# Nixie_Driver.net
KiCad netlist of a schematic drawn in Altium Designer
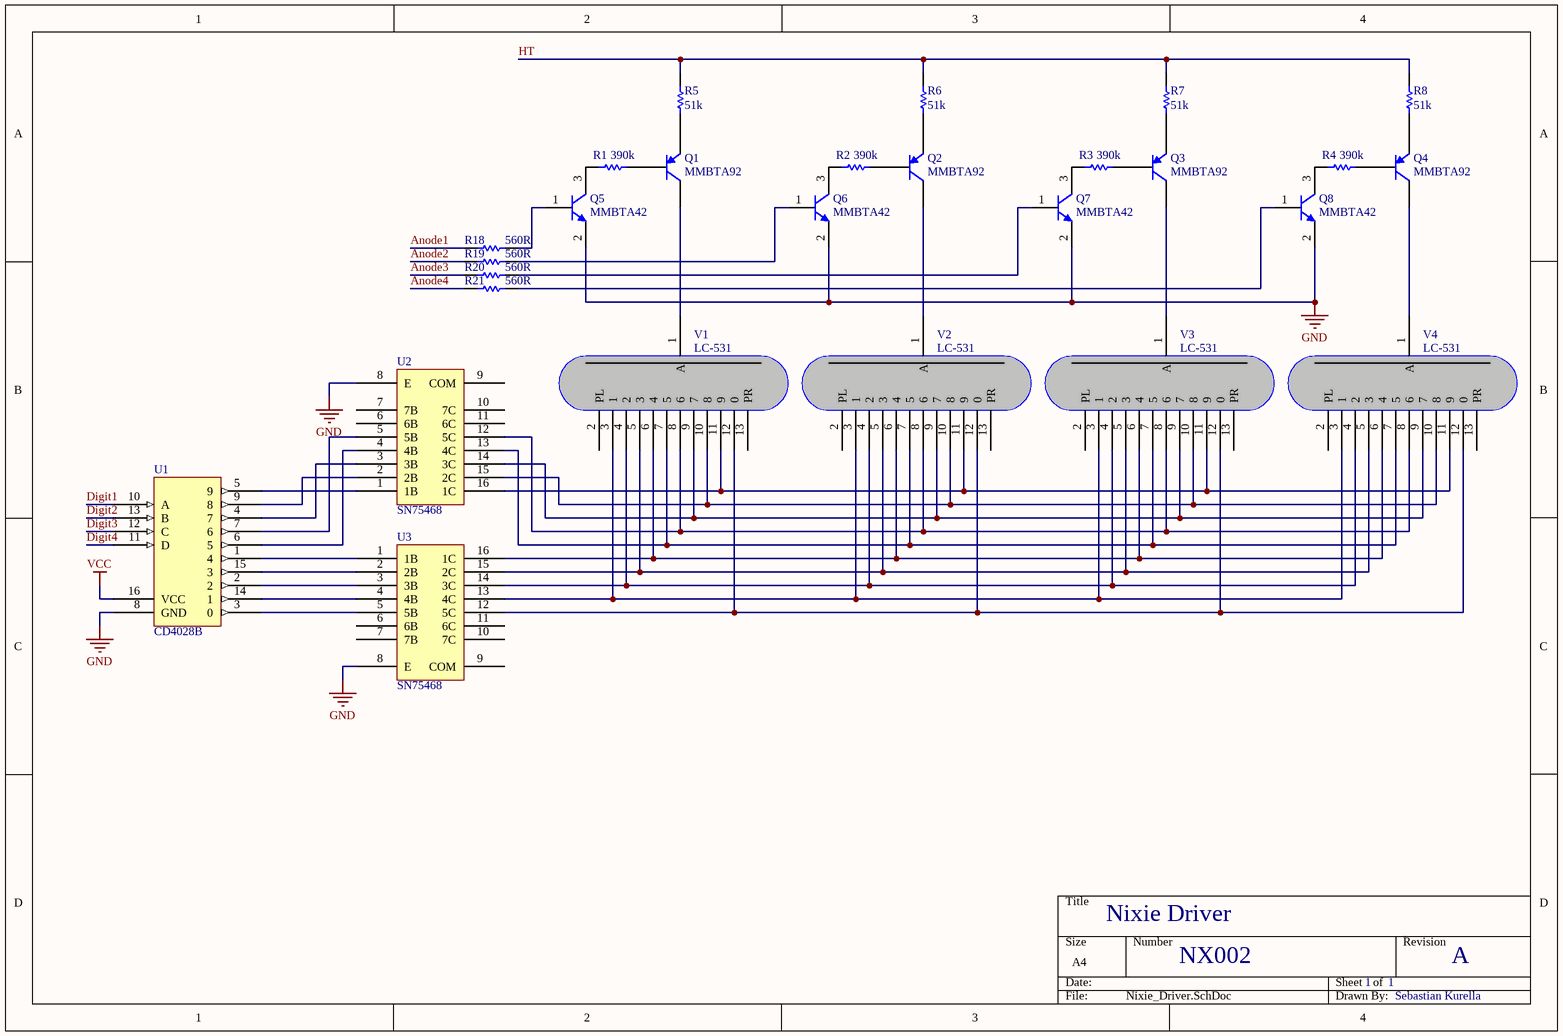
[diagram p0: Nixie_Driver.SchDoc]

(export (version "E")
  (design (tool "Eeschema 10.0.6"))
  (components
    (comp (ref "Q1")
      (value "MMBTA92")
      (footprint "INF-SOT23_M")
      (description "PNP Silicon High-Voltage Transistor, 300 V VCEO, 500 mA IC, SOT23, Reel, Green")
      (fields (field (name "MANUFACTURER") "Infineon"))
      (libsource (lib "Altium Content Vault") (part "CMP-1197-00010-1"))
    )
    (comp (ref "Q2")
      (value "MMBTA92")
      (footprint "INF-SOT23_M")
      (description "PNP Silicon High-Voltage Transistor, 300 V VCEO, 500 mA IC, SOT23, Reel, Green")
      (fields (field (name "MANUFACTURER") "Infineon"))
      (libsource (lib "Altium Content Vault") (part "CMP-1197-00010-1"))
    )
    (comp (ref "Q3")
      (value "MMBTA92")
      (footprint "INF-SOT23_M")
      (description "PNP Silicon High-Voltage Transistor, 300 V VCEO, 500 mA IC, SOT23, Reel, Green")
      (fields (field (name "MANUFACTURER") "Infineon"))
      (libsource (lib "Altium Content Vault") (part "CMP-1197-00010-1"))
    )
    (comp (ref "Q4")
      (value "MMBTA92")
      (footprint "INF-SOT23_M")
      (description "PNP Silicon High-Voltage Transistor, 300 V VCEO, 500 mA IC, SOT23, Reel, Green")
      (fields (field (name "MANUFACTURER") "Infineon"))
      (libsource (lib "Altium Content Vault") (part "CMP-1197-00010-1"))
    )
    (comp (ref "Q5")
      (value "MMBTA42")
      (footprint "ONSC-SOT-23-3-318-08_V")
      (description "High Voltage Transistor, NPN Silicon, 3-Pin SOT-23, Pb-Free, Tape and Reel")
      (fields (field (name "MANUFACTURER") "On Semiconductor"))
      (libsource (lib "Altium Content Vault") (part "CMP-1048-00662-1"))
    )
    (comp (ref "Q6")
      (value "MMBTA42")
      (footprint "ONSC-SOT-23-3-318-08_V")
      (description "High Voltage Transistor, NPN Silicon, 3-Pin SOT-23, Pb-Free, Tape and Reel")
      (fields (field (name "MANUFACTURER") "On Semiconductor"))
      (libsource (lib "Altium Content Vault") (part "CMP-1048-00662-1"))
    )
    (comp (ref "Q7")
      (value "MMBTA42")
      (footprint "ONSC-SOT-23-3-318-08_V")
      (description "High Voltage Transistor, NPN Silicon, 3-Pin SOT-23, Pb-Free, Tape and Reel")
      (fields (field (name "MANUFACTURER") "On Semiconductor"))
      (libsource (lib "Altium Content Vault") (part "CMP-1048-00662-1"))
    )
    (comp (ref "Q8")
      (value "MMBTA42")
      (footprint "ONSC-SOT-23-3-318-08_V")
      (description "High Voltage Transistor, NPN Silicon, 3-Pin SOT-23, Pb-Free, Tape and Reel")
      (fields (field (name "MANUFACTURER") "On Semiconductor"))
      (libsource (lib "Altium Content Vault") (part "CMP-1048-00662-1"))
    )
    (comp (ref "R1")
      (value "390k")
      (footprint "RESC0805(2012)_M")
      (description "390K 0.125W 5% 0805 (2012 Metric)  SMD")
      (fields (field (name "TOLERANCE") "5 %") (field (name "POWER") "0.125 W"))
      (libsource (lib "Altium Content Vault") (part "CMP-1013-00136-1"))
    )
    (comp (ref "R2")
      (value "390k")
      (footprint "RESC0805(2012)_M")
      (description "390K 0.125W 5% 0805 (2012 Metric)  SMD")
      (fields (field (name "TOLERANCE") "5 %") (field (name "POWER") "0.125 W"))
      (libsource (lib "Altium Content Vault") (part "CMP-1013-00136-1"))
    )
    (comp (ref "R3")
      (value "390k")
      (footprint "RESC0805(2012)_M")
      (description "390K 0.125W 5% 0805 (2012 Metric)  SMD")
      (fields (field (name "TOLERANCE") "5 %") (field (name "POWER") "0.125 W"))
      (libsource (lib "Altium Content Vault") (part "CMP-1013-00136-1"))
    )
    (comp (ref "R4")
      (value "390k")
      (footprint "RESC0805(2012)_M")
      (description "390K 0.125W 5% 0805 (2012 Metric)  SMD")
      (fields (field (name "TOLERANCE") "5 %") (field (name "POWER") "0.125 W"))
      (libsource (lib "Altium Content Vault") (part "CMP-1013-00136-1"))
    )
    (comp (ref "R5")
      (value "51k")
      (footprint "RESC0805(2012)_M")
      (description "51K 0.125W 5% 0805 (2012 Metric)  SMD")
      (fields (field (name "POWER") "0.125 W") (field (name "TOLERANCE") "5 %"))
      (libsource (lib "Altium Content Vault") (part "CMP-1013-00115-1"))
    )
    (comp (ref "R6")
      (value "51k")
      (footprint "RESC0805(2012)_M")
      (description "51K 0.125W 5% 0805 (2012 Metric)  SMD")
      (fields (field (name "POWER") "0.125 W") (field (name "TOLERANCE") "5 %"))
      (libsource (lib "Altium Content Vault") (part "CMP-1013-00115-1"))
    )
    (comp (ref "R7")
      (value "51k")
      (footprint "RESC0805(2012)_M")
      (description "51K 0.125W 5% 0805 (2012 Metric)  SMD")
      (fields (field (name "POWER") "0.125 W") (field (name "TOLERANCE") "5 %"))
      (libsource (lib "Altium Content Vault") (part "CMP-1013-00115-1"))
    )
    (comp (ref "R8")
      (value "51k")
      (footprint "RESC0805(2012)_M")
      (description "51K 0.125W 5% 0805 (2012 Metric)  SMD")
      (fields (field (name "POWER") "0.125 W") (field (name "TOLERANCE") "5 %"))
      (libsource (lib "Altium Content Vault") (part "CMP-1013-00115-1"))
    )
    (comp (ref "R18")
      (value "560R")
      (footprint "RESC0805(2012)_M")
      (description "560R 0.125W 5% 0805 (2012 Metric)  SMD")
      (fields (field (name "POWER") "0.125 W") (field (name "TOLERANCE") "5 %"))
      (libsource (lib "Altium Content Vault") (part "CMP-1013-00068-1"))
    )
    (comp (ref "R19")
      (value "560R")
      (footprint "RESC0805(2012)_M")
      (description "560R 0.125W 5% 0805 (2012 Metric)  SMD")
      (fields (field (name "POWER") "0.125 W") (field (name "TOLERANCE") "5 %"))
      (libsource (lib "Altium Content Vault") (part "CMP-1013-00068-1"))
    )
    (comp (ref "R20")
      (value "560R")
      (footprint "RESC0805(2012)_M")
      (description "560R 0.125W 5% 0805 (2012 Metric)  SMD")
      (fields (field (name "POWER") "0.125 W") (field (name "TOLERANCE") "5 %"))
      (libsource (lib "Altium Content Vault") (part "CMP-1013-00068-1"))
    )
    (comp (ref "R21")
      (value "560R")
      (footprint "RESC0805(2012)_M")
      (description "560R 0.125W 5% 0805 (2012 Metric)  SMD")
      (fields (field (name "POWER") "0.125 W") (field (name "TOLERANCE") "5 %"))
      (libsource (lib "Altium Content Vault") (part "CMP-1013-00068-1"))
    )
    (comp (ref "U1")
      (value "CD4028B")
      (footprint "CD4028B")
      (description "BCD-to-decimal driver")
      (libsource (lib "Nixie_Driver") (part "CD4028B"))
    )
    (comp (ref "U2")
      (value "SN75468")
      (footprint "SN7546x")
      (description "Darlington Transistor Array")
      (libsource (lib "") (part "SN7546x_1"))
    )
    (comp (ref "U3")
      (value "SN75468")
      (footprint "SN7546x")
      (description "Darlington Transistor Array")
      (libsource (lib "Nixie_Driver") (part "SN7546x"))
    )
    (comp (ref "V1")
      (value "LC-531")
      (footprint "LC-531")
      (description "Nixie tube")
      (libsource (lib "Nixie_Driver") (part "LC531"))
    )
    (comp (ref "V2")
      (value "LC-531")
      (footprint "LC-531")
      (description "Nixie tube")
      (libsource (lib "Nixie_Driver") (part "LC531"))
    )
    (comp (ref "V3")
      (value "LC-531")
      (footprint "LC-531")
      (description "Nixie tube")
      (libsource (lib "Nixie_Driver") (part "LC531"))
    )
    (comp (ref "V4")
      (value "LC-531")
      (footprint "LC-531")
      (description "Nixie tube")
      (libsource (lib "Nixie_Driver") (part "LC531"))
    )
  )
  (nets
    (net (code "1") (name "/Anode1") (class "Default")
      (node (ref "R18") (pin "1") (pinfunction "1_1") (pintype "passive"))
    )
    (net (code "2") (name "/Anode2") (class "Default")
      (node (ref "R19") (pin "1") (pinfunction "1_1") (pintype "passive"))
    )
    (net (code "3") (name "/Anode3") (class "Default")
      (node (ref "R20") (pin "1") (pinfunction "1_1") (pintype "passive"))
    )
    (net (code "4") (name "/Anode4") (class "Default")
      (node (ref "R21") (pin "1") (pinfunction "1_1") (pintype "passive"))
    )
    (net (code "5") (name "/Digit1") (class "Default")
      (node (ref "U1") (pin "10") (pinfunction "A_10") (pintype "input"))
    )
    (net (code "6") (name "/Digit2") (class "Default")
      (node (ref "U1") (pin "13") (pinfunction "B_13") (pintype "input"))
    )
    (net (code "7") (name "/Digit3") (class "Default")
      (node (ref "U1") (pin "12") (pinfunction "C_12") (pintype "input"))
    )
    (net (code "8") (name "/Digit4") (class "Default")
      (node (ref "U1") (pin "11") (pinfunction "D_11") (pintype "input"))
    )
    (net (code "9") (name "/HT") (class "Default")
      (node (ref "R5") (pin "2") (pinfunction "2_2") (pintype "passive"))
      (node (ref "R6") (pin "2") (pinfunction "2_2") (pintype "passive"))
      (node (ref "R7") (pin "2") (pinfunction "2_2") (pintype "passive"))
      (node (ref "R8") (pin "2") (pinfunction "2_2") (pintype "passive"))
    )
    (net (code "10") (name "GND") (class "Default")
      (node (ref "Q5") (pin "2") (pinfunction "E_2") (pintype "passive"))
      (node (ref "Q6") (pin "2") (pinfunction "E_2") (pintype "passive"))
      (node (ref "Q7") (pin "2") (pinfunction "E_2") (pintype "passive"))
      (node (ref "Q8") (pin "2") (pinfunction "E_2") (pintype "passive"))
      (node (ref "U1") (pin "8") (pinfunction "GND_8") (pintype "power_in"))
      (node (ref "U2") (pin "8") (pinfunction "E_8") (pintype "passive"))
      (node (ref "U3") (pin "8") (pinfunction "E_8") (pintype "passive"))
    )
    (net (code "11") (name "Net-(Q1-B)") (class "Default")
      (node (ref "Q1") (pin "1") (pinfunction "B_1") (pintype "passive"))
      (node (ref "R1") (pin "2") (pinfunction "2_2") (pintype "passive"))
    )
    (net (code "12") (name "Net-(Q1-C)") (class "Default")
      (node (ref "Q1") (pin "3") (pinfunction "C_3") (pintype "passive"))
      (node (ref "V1") (pin "1") (pinfunction "A_1") (pintype "passive"))
    )
    (net (code "13") (name "Net-(Q1-E)") (class "Default")
      (node (ref "Q1") (pin "2") (pinfunction "E_2") (pintype "passive"))
      (node (ref "R5") (pin "1") (pinfunction "1_1") (pintype "passive"))
    )
    (net (code "14") (name "Net-(Q2-B)") (class "Default")
      (node (ref "Q2") (pin "1") (pinfunction "B_1") (pintype "passive"))
      (node (ref "R2") (pin "2") (pinfunction "2_2") (pintype "passive"))
    )
    (net (code "15") (name "Net-(Q2-C)") (class "Default")
      (node (ref "Q2") (pin "3") (pinfunction "C_3") (pintype "passive"))
      (node (ref "V2") (pin "1") (pinfunction "A_1") (pintype "passive"))
    )
    (net (code "16") (name "Net-(Q2-E)") (class "Default")
      (node (ref "Q2") (pin "2") (pinfunction "E_2") (pintype "passive"))
      (node (ref "R6") (pin "1") (pinfunction "1_1") (pintype "passive"))
    )
    (net (code "17") (name "Net-(Q3-B)") (class "Default")
      (node (ref "Q3") (pin "1") (pinfunction "B_1") (pintype "passive"))
      (node (ref "R3") (pin "2") (pinfunction "2_2") (pintype "passive"))
    )
    (net (code "18") (name "Net-(Q3-C)") (class "Default")
      (node (ref "Q3") (pin "3") (pinfunction "C_3") (pintype "passive"))
      (node (ref "V3") (pin "1") (pinfunction "A_1") (pintype "passive"))
    )
    (net (code "19") (name "Net-(Q3-E)") (class "Default")
      (node (ref "Q3") (pin "2") (pinfunction "E_2") (pintype "passive"))
      (node (ref "R7") (pin "1") (pinfunction "1_1") (pintype "passive"))
    )
    (net (code "20") (name "Net-(Q4-B)") (class "Default")
      (node (ref "Q4") (pin "1") (pinfunction "B_1") (pintype "passive"))
      (node (ref "R4") (pin "2") (pinfunction "2_2") (pintype "passive"))
    )
    (net (code "21") (name "Net-(Q4-C)") (class "Default")
      (node (ref "Q4") (pin "3") (pinfunction "C_3") (pintype "passive"))
      (node (ref "V4") (pin "1") (pinfunction "A_1") (pintype "passive"))
    )
    (net (code "22") (name "Net-(Q4-E)") (class "Default")
      (node (ref "Q4") (pin "2") (pinfunction "E_2") (pintype "passive"))
      (node (ref "R8") (pin "1") (pinfunction "1_1") (pintype "passive"))
    )
    (net (code "23") (name "Net-(Q5-B)") (class "Default")
      (node (ref "Q5") (pin "1") (pinfunction "B_1") (pintype "passive"))
      (node (ref "R18") (pin "2") (pinfunction "2_2") (pintype "passive"))
    )
    (net (code "24") (name "Net-(Q5-C)") (class "Default")
      (node (ref "Q5") (pin "3") (pinfunction "C_3") (pintype "passive"))
      (node (ref "R1") (pin "1") (pinfunction "1_1") (pintype "passive"))
    )
    (net (code "25") (name "Net-(Q6-B)") (class "Default")
      (node (ref "Q6") (pin "1") (pinfunction "B_1") (pintype "passive"))
      (node (ref "R19") (pin "2") (pinfunction "2_2") (pintype "passive"))
    )
    (net (code "26") (name "Net-(Q6-C)") (class "Default")
      (node (ref "Q6") (pin "3") (pinfunction "C_3") (pintype "passive"))
      (node (ref "R2") (pin "1") (pinfunction "1_1") (pintype "passive"))
    )
    (net (code "27") (name "Net-(Q7-B)") (class "Default")
      (node (ref "Q7") (pin "1") (pinfunction "B_1") (pintype "passive"))
      (node (ref "R20") (pin "2") (pinfunction "2_2") (pintype "passive"))
    )
    (net (code "28") (name "Net-(Q7-C)") (class "Default")
      (node (ref "Q7") (pin "3") (pinfunction "C_3") (pintype "passive"))
      (node (ref "R3") (pin "1") (pinfunction "1_1") (pintype "passive"))
    )
    (net (code "29") (name "Net-(Q8-B)") (class "Default")
      (node (ref "Q8") (pin "1") (pinfunction "B_1") (pintype "passive"))
      (node (ref "R21") (pin "2") (pinfunction "2_2") (pintype "passive"))
    )
    (net (code "30") (name "Net-(Q8-C)") (class "Default")
      (node (ref "Q8") (pin "3") (pinfunction "C_3") (pintype "passive"))
      (node (ref "R4") (pin "1") (pinfunction "1_1") (pintype "passive"))
    )
    (net (code "31") (name "Net-(U1-0)") (class "Default")
      (node (ref "U1") (pin "3") (pinfunction "0_3") (pintype "output"))
      (node (ref "U3") (pin "5") (pinfunction "5B_5") (pintype "passive"))
    )
    (net (code "32") (name "Net-(U1-1)") (class "Default")
      (node (ref "U1") (pin "14") (pinfunction "1_14") (pintype "output"))
      (node (ref "U3") (pin "4") (pinfunction "4B_4") (pintype "passive"))
    )
    (net (code "33") (name "Net-(U1-3)") (class "Default")
      (node (ref "U1") (pin "15") (pinfunction "3_15") (pintype "output"))
      (node (ref "U3") (pin "2") (pinfunction "2B_2") (pintype "passive"))
    )
    (net (code "34") (name "Net-(U1-4)") (class "Default")
      (node (ref "U1") (pin "1") (pinfunction "4_1") (pintype "output"))
      (node (ref "U3") (pin "1") (pinfunction "1B_1") (pintype "passive"))
    )
    (net (code "35") (name "Net-(U1-5)") (class "Default")
      (node (ref "U1") (pin "6") (pinfunction "5_6") (pintype "output"))
      (node (ref "U2") (pin "4") (pinfunction "4B_4") (pintype "passive"))
    )
    (net (code "36") (name "Net-(U1-6)") (class "Default")
      (node (ref "U1") (pin "7") (pinfunction "6_7") (pintype "output"))
      (node (ref "U2") (pin "5") (pinfunction "5B_5") (pintype "passive"))
    )
    (net (code "37") (name "Net-(U1-7)") (class "Default")
      (node (ref "U1") (pin "4") (pinfunction "7_4") (pintype "output"))
      (node (ref "U2") (pin "3") (pinfunction "3B_3") (pintype "passive"))
    )
    (net (code "38") (name "Net-(U1-8)") (class "Default")
      (node (ref "U1") (pin "9") (pinfunction "8_9") (pintype "output"))
      (node (ref "U2") (pin "2") (pinfunction "2B_2") (pintype "passive"))
    )
    (net (code "39") (name "Net-(U1-9)") (class "Default")
      (node (ref "U1") (pin "5") (pinfunction "9_5") (pintype "output"))
      (node (ref "U2") (pin "1") (pinfunction "1B_1") (pintype "passive"))
    )
    (net (code "40") (name "Net-(U2-1C)") (class "Default")
      (node (ref "U2") (pin "16") (pinfunction "1C_16") (pintype "passive"))
      (node (ref "V1") (pin "11") (pinfunction "9_11") (pintype "passive"))
      (node (ref "V2") (pin "11") (pinfunction "9_11") (pintype "passive"))
      (node (ref "V3") (pin "11") (pinfunction "9_11") (pintype "passive"))
      (node (ref "V4") (pin "11") (pinfunction "9_11") (pintype "passive"))
    )
    (net (code "41") (name "Net-(U2-2C)") (class "Default")
      (node (ref "U2") (pin "15") (pinfunction "2C_15") (pintype "passive"))
      (node (ref "V1") (pin "10") (pinfunction "8_10") (pintype "passive"))
      (node (ref "V2") (pin "10") (pinfunction "8_10") (pintype "passive"))
      (node (ref "V3") (pin "10") (pinfunction "8_10") (pintype "passive"))
      (node (ref "V4") (pin "10") (pinfunction "8_10") (pintype "passive"))
    )
    (net (code "42") (name "Net-(U2-3C)") (class "Default")
      (node (ref "U2") (pin "14") (pinfunction "3C_14") (pintype "passive"))
      (node (ref "V1") (pin "9") (pinfunction "7_9") (pintype "passive"))
      (node (ref "V2") (pin "9") (pinfunction "7_9") (pintype "passive"))
      (node (ref "V3") (pin "9") (pinfunction "7_9") (pintype "passive"))
      (node (ref "V4") (pin "9") (pinfunction "7_9") (pintype "passive"))
    )
    (net (code "43") (name "Net-(U2-4C)") (class "Default")
      (node (ref "U2") (pin "13") (pinfunction "4C_13") (pintype "passive"))
      (node (ref "V1") (pin "7") (pinfunction "5_7") (pintype "passive"))
      (node (ref "V2") (pin "7") (pinfunction "5_7") (pintype "passive"))
      (node (ref "V3") (pin "7") (pinfunction "5_7") (pintype "passive"))
      (node (ref "V4") (pin "7") (pinfunction "5_7") (pintype "passive"))
    )
    (net (code "44") (name "Net-(U2-5C)") (class "Default")
      (node (ref "U2") (pin "12") (pinfunction "5C_12") (pintype "passive"))
      (node (ref "V1") (pin "8") (pinfunction "6_8") (pintype "passive"))
      (node (ref "V2") (pin "8") (pinfunction "6_8") (pintype "passive"))
      (node (ref "V3") (pin "8") (pinfunction "6_8") (pintype "passive"))
      (node (ref "V4") (pin "8") (pinfunction "6_8") (pintype "passive"))
    )
    (net (code "45") (name "Net-(U3-1C)") (class "Default")
      (node (ref "U3") (pin "16") (pinfunction "1C_16") (pintype "passive"))
      (node (ref "V1") (pin "6") (pinfunction "4_6") (pintype "passive"))
      (node (ref "V2") (pin "6") (pinfunction "4_6") (pintype "passive"))
      (node (ref "V3") (pin "6") (pinfunction "4_6") (pintype "passive"))
      (node (ref "V4") (pin "6") (pinfunction "4_6") (pintype "passive"))
    )
    (net (code "46") (name "Net-(U3-2C)") (class "Default")
      (node (ref "U3") (pin "15") (pinfunction "2C_15") (pintype "passive"))
      (node (ref "V1") (pin "5") (pinfunction "3_5") (pintype "passive"))
      (node (ref "V2") (pin "5") (pinfunction "3_5") (pintype "passive"))
      (node (ref "V3") (pin "5") (pinfunction "3_5") (pintype "passive"))
      (node (ref "V4") (pin "5") (pinfunction "3_5") (pintype "passive"))
    )
    (net (code "47") (name "Net-(U3-3B)") (class "Default")
      (node (ref "U1") (pin "2") (pinfunction "2_2") (pintype "output"))
      (node (ref "U3") (pin "3") (pinfunction "3B_3") (pintype "passive"))
    )
    (net (code "48") (name "Net-(U3-3C)") (class "Default")
      (node (ref "U3") (pin "14") (pinfunction "3C_14") (pintype "passive"))
      (node (ref "V1") (pin "4") (pinfunction "2_4") (pintype "passive"))
      (node (ref "V2") (pin "4") (pinfunction "2_4") (pintype "passive"))
      (node (ref "V3") (pin "4") (pinfunction "2_4") (pintype "passive"))
      (node (ref "V4") (pin "4") (pinfunction "2_4") (pintype "passive"))
    )
    (net (code "49") (name "Net-(U3-4C)") (class "Default")
      (node (ref "U3") (pin "13") (pinfunction "4C_13") (pintype "passive"))
      (node (ref "V1") (pin "3") (pinfunction "1_3") (pintype "passive"))
      (node (ref "V2") (pin "3") (pinfunction "1_3") (pintype "passive"))
      (node (ref "V3") (pin "3") (pinfunction "1_3") (pintype "passive"))
      (node (ref "V4") (pin "3") (pinfunction "1_3") (pintype "passive"))
    )
    (net (code "50") (name "Net-(U3-5C)") (class "Default")
      (node (ref "U3") (pin "12") (pinfunction "5C_12") (pintype "passive"))
      (node (ref "V1") (pin "12") (pinfunction "0_12") (pintype "passive"))
      (node (ref "V2") (pin "12") (pinfunction "0_12") (pintype "passive"))
      (node (ref "V3") (pin "12") (pinfunction "0_12") (pintype "passive"))
      (node (ref "V4") (pin "12") (pinfunction "0_12") (pintype "passive"))
    )
    (net (code "51") (name "VCC") (class "Default")
      (node (ref "U1") (pin "16") (pinfunction "VCC_16") (pintype "power_in"))
    )
    (net (code "52") (name "unconnected-(U2-6B-Pad6)") (class "Default")
      (node (ref "U2") (pin "6") (pinfunction "6B_6") (pintype "passive"))
    )
    (net (code "53") (name "unconnected-(U2-6C-Pad11)") (class "Default")
      (node (ref "U2") (pin "11") (pinfunction "6C_11") (pintype "passive"))
    )
    (net (code "54") (name "unconnected-(U2-7B-Pad7)") (class "Default")
      (node (ref "U2") (pin "7") (pinfunction "7B_7") (pintype "passive"))
    )
    (net (code "55") (name "unconnected-(U2-7C-Pad10)") (class "Default")
      (node (ref "U2") (pin "10") (pinfunction "7C_10") (pintype "passive"))
    )
    (net (code "56") (name "unconnected-(U2-COM-Pad9)") (class "Default")
      (node (ref "U2") (pin "9") (pinfunction "COM_9") (pintype "passive"))
    )
    (net (code "57") (name "unconnected-(U3-6B-Pad6)") (class "Default")
      (node (ref "U3") (pin "6") (pinfunction "6B_6") (pintype "passive"))
    )
    (net (code "58") (name "unconnected-(U3-6C-Pad11)") (class "Default")
      (node (ref "U3") (pin "11") (pinfunction "6C_11") (pintype "passive"))
    )
    (net (code "59") (name "unconnected-(U3-7B-Pad7)") (class "Default")
      (node (ref "U3") (pin "7") (pinfunction "7B_7") (pintype "passive"))
    )
    (net (code "60") (name "unconnected-(U3-7C-Pad10)") (class "Default")
      (node (ref "U3") (pin "10") (pinfunction "7C_10") (pintype "passive"))
    )
    (net (code "61") (name "unconnected-(U3-COM-Pad9)") (class "Default")
      (node (ref "U3") (pin "9") (pinfunction "COM_9") (pintype "passive"))
    )
    (net (code "62") (name "unconnected-(V1-PL-Pad2)") (class "Default")
      (node (ref "V1") (pin "2") (pinfunction "PL_2") (pintype "passive"))
    )
    (net (code "63") (name "unconnected-(V1-PR-Pad13)") (class "Default")
      (node (ref "V1") (pin "13") (pinfunction "PR_13") (pintype "passive"))
    )
    (net (code "64") (name "unconnected-(V2-PL-Pad2)") (class "Default")
      (node (ref "V2") (pin "2") (pinfunction "PL_2") (pintype "passive"))
    )
    (net (code "65") (name "unconnected-(V2-PR-Pad13)") (class "Default")
      (node (ref "V2") (pin "13") (pinfunction "PR_13") (pintype "passive"))
    )
    (net (code "66") (name "unconnected-(V3-PL-Pad2)") (class "Default")
      (node (ref "V3") (pin "2") (pinfunction "PL_2") (pintype "passive"))
    )
    (net (code "67") (name "unconnected-(V3-PR-Pad13)") (class "Default")
      (node (ref "V3") (pin "13") (pinfunction "PR_13") (pintype "passive"))
    )
    (net (code "68") (name "unconnected-(V4-PL-Pad2)") (class "Default")
      (node (ref "V4") (pin "2") (pinfunction "PL_2") (pintype "passive"))
    )
    (net (code "69") (name "unconnected-(V4-PR-Pad13)") (class "Default")
      (node (ref "V4") (pin "13") (pinfunction "PR_13") (pintype "passive"))
    )
  )
)
